# vss_adapter.net
KiCad netlist of a schematic drawn in EAGLE
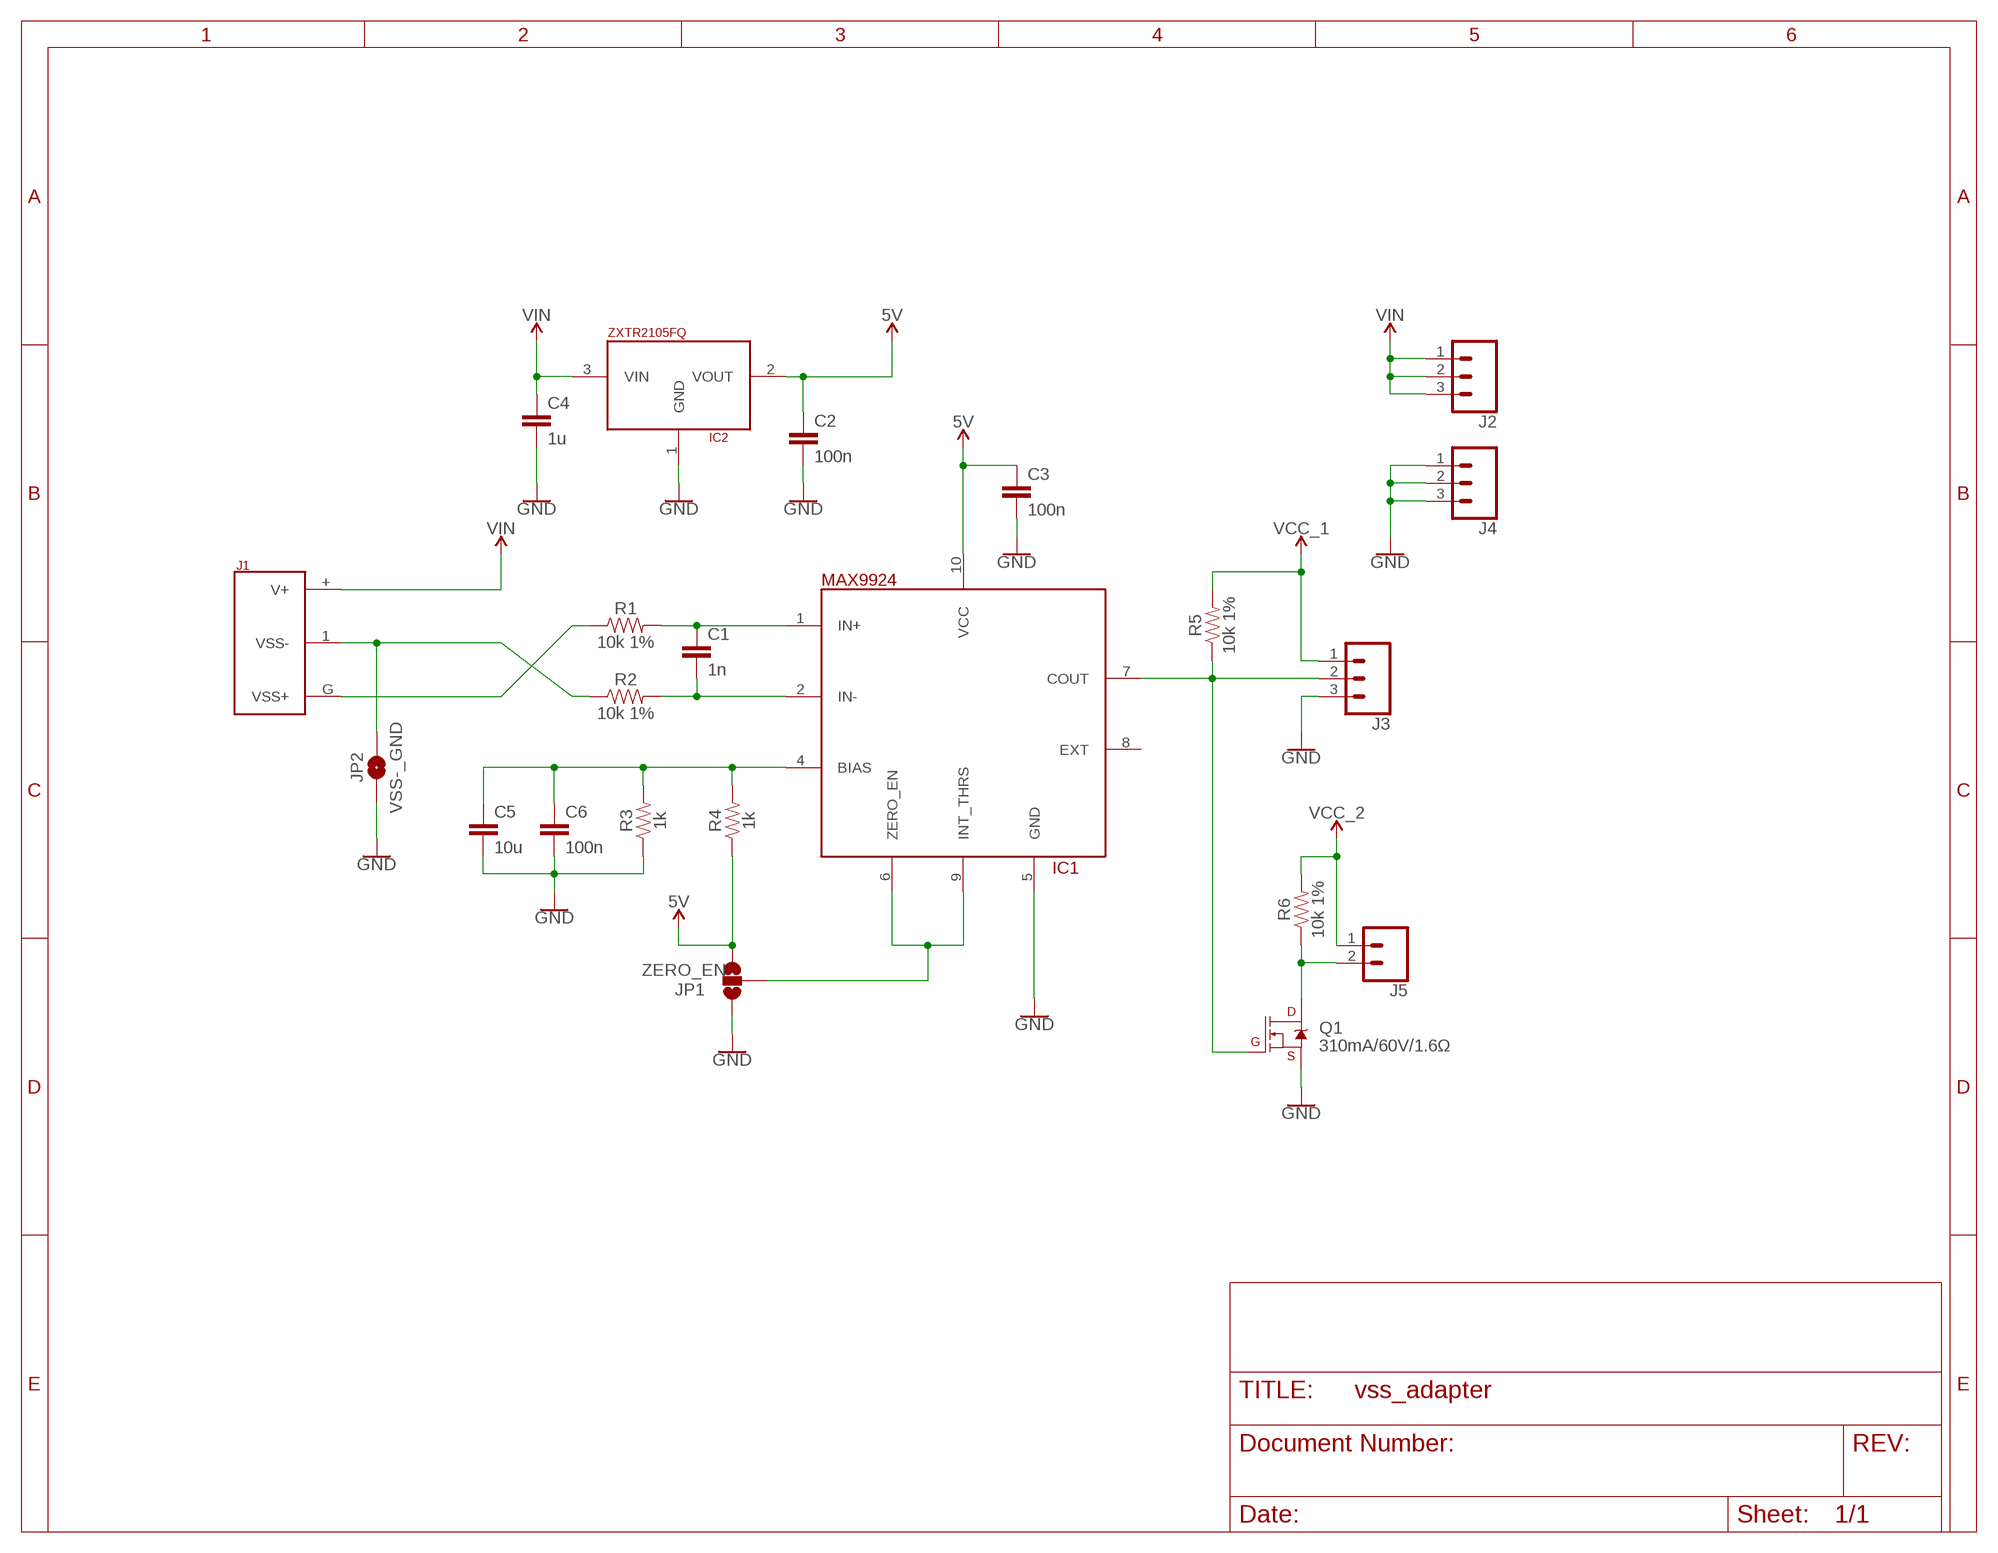
[diagram p0: schematic, sheet 1]

(export (version "E")
  (design (tool "Eeschema 10.0.6"))
  (components
    (comp (ref "C1")
      (value "1n")
      (footprint "eagle-import:0603")
      (libsource (lib "eagle-import") (part "CL10B102KB8NNWC"))
    )
    (comp (ref "C2")
      (value "100n")
      (footprint "eagle-import:0603")
      (libsource (lib "eagle-import") (part "CL10B104MB8NNNC"))
    )
    (comp (ref "C3")
      (value "100n")
      (footprint "eagle-import:0603")
      (libsource (lib "eagle-import") (part "CL10B104MB8NNNC"))
    )
    (comp (ref "C4")
      (value "1u")
      (footprint "eagle-import:0603")
      (libsource (lib "eagle-import") (part "CL10A105KA8NNNC"))
    )
    (comp (ref "C5")
      (value "10u")
      (footprint "eagle-import:0603")
      (libsource (lib "eagle-import") (part "CL10B106MQ8NRNC"))
    )
    (comp (ref "C6")
      (value "100n")
      (footprint "eagle-import:0603")
      (libsource (lib "eagle-import") (part "CL10B104MB8NNNC"))
    )
    (comp (ref "IC1")
      (value "MAX9924")
      (footprint "eagle-import:UMAX10")
      (libsource (lib "eagle-import") (part "MAX9924"))
    )
    (comp (ref "IC2")
      (value "ZXTR2105FQ")
      (footprint "eagle-import:SOT23")
      (libsource (lib "eagle-import") (part "ZXTR2105FQ"))
    )
    (comp (ref "J1")
      (value "VOLVO_CONN_VSS")
      (footprint "eagle-import:VOLVO_CONN_VSS")
      (libsource (lib "eagle-import") (part "VOLVO_CONN_VSS"))
    )
    (comp (ref "J2")
      (value "CONN_031X03_LARGE")
      (footprint "eagle-import:1X03_LARGE")
      (libsource (lib "eagle-import") (part "CONN_031X03_LARGE"))
    )
    (comp (ref "J3")
      (value "CONN_031X03_LARGE")
      (footprint "eagle-import:1X03_LARGE")
      (libsource (lib "eagle-import") (part "CONN_031X03_LARGE"))
    )
    (comp (ref "J4")
      (value "CONN_031X03_LARGE")
      (footprint "eagle-import:1X03_LARGE")
      (libsource (lib "eagle-import") (part "CONN_031X03_LARGE"))
    )
    (comp (ref "J5")
      (value "CONN_02LARGE")
      (footprint "eagle-import:1X02_LARGE")
      (libsource (lib "eagle-import") (part "CONN_02LARGE"))
    )
    (comp (ref "JP1")
      (value "ZERO_EN")
      (footprint "eagle-import:SMT-JUMPER_3_NO_SILK")
      (libsource (lib "eagle-import") (part "JUMPER-SMT_3_NO_SILK"))
    )
    (comp (ref "JP2")
      (value "VSS-_GND")
      (footprint "eagle-import:SMT-JUMPER_2_NO_SILK")
      (libsource (lib "eagle-import") (part "JUMPER-SMT_2_NO_SILK"))
    )
    (comp (ref "Q1")
      (value "310mA/60V/1.6Ω")
      (footprint "eagle-import:SOT323")
      (libsource (lib "eagle-import") (part "MOSFET-NCH-2N7002PW"))
    )
    (comp (ref "R1")
      (value "10k 1%")
      (footprint "eagle-import:0603")
      (libsource (lib "eagle-import") (part "RC0603FR-1010KL"))
    )
    (comp (ref "R2")
      (value "10k 1%")
      (footprint "eagle-import:0603")
      (libsource (lib "eagle-import") (part "RC0603FR-1010KL"))
    )
    (comp (ref "R3")
      (value "1k")
      (footprint "eagle-import:0603")
      (libsource (lib "eagle-import") (part "RC0603JR-071KL"))
    )
    (comp (ref "R4")
      (value "1k")
      (footprint "eagle-import:0603")
      (libsource (lib "eagle-import") (part "RC0603JR-071KL"))
    )
    (comp (ref "R5")
      (value "10k 1%")
      (footprint "eagle-import:0603")
      (libsource (lib "eagle-import") (part "RC0603FR-1010KL"))
    )
    (comp (ref "R6")
      (value "10k 1%")
      (footprint "eagle-import:0603")
      (libsource (lib "eagle-import") (part "RC0603FR-1010KL"))
    )
  )
  (nets
    (net (code "1") (name "5V") (class "Default")
      (node (ref "C2") (pin "1") (pinfunction "1_1") (pintype "passive"))
      (node (ref "C3") (pin "1") (pinfunction "1_1") (pintype "passive"))
      (node (ref "IC1") (pin "10") (pinfunction "VCC_10") (pintype "bidirectional"))
      (node (ref "IC2") (pin "2") (pinfunction "VOUT_2") (pintype "bidirectional"))
      (node (ref "JP1") (pin "3") (pinfunction "3_3") (pintype "passive"))
      (node (ref "R4") (pin "1") (pinfunction "1_1") (pintype "passive"))
    )
    (net (code "2") (name "GND") (class "Default")
      (node (ref "C2") (pin "2") (pinfunction "2_2") (pintype "passive"))
      (node (ref "C3") (pin "2") (pinfunction "2_2") (pintype "passive"))
      (node (ref "C4") (pin "2") (pinfunction "2_2") (pintype "passive"))
      (node (ref "C5") (pin "2") (pinfunction "2_2") (pintype "passive"))
      (node (ref "C6") (pin "2") (pinfunction "2_2") (pintype "passive"))
      (node (ref "IC1") (pin "5") (pinfunction "GND_5") (pintype "bidirectional"))
      (node (ref "IC2") (pin "1") (pinfunction "GND_1") (pintype "bidirectional"))
      (node (ref "J3") (pin "3") (pinfunction "3_3") (pintype "passive"))
      (node (ref "J4") (pin "1") (pinfunction "1_1") (pintype "passive"))
      (node (ref "J4") (pin "2") (pinfunction "2_2") (pintype "passive"))
      (node (ref "J4") (pin "3") (pinfunction "3_3") (pintype "passive"))
      (node (ref "JP1") (pin "1") (pinfunction "1_1") (pintype "passive"))
      (node (ref "JP2") (pin "1") (pinfunction "1_1") (pintype "passive"))
      (node (ref "Q1") (pin "2") (pinfunction "S_2") (pintype "bidirectional"))
      (node (ref "R3") (pin "1") (pinfunction "1_1") (pintype "passive"))
    )
    (net (code "3") (name "Net-(IC1-BIAS)") (class "Default")
      (node (ref "C5") (pin "1") (pinfunction "1_1") (pintype "passive"))
      (node (ref "C6") (pin "1") (pinfunction "1_1") (pintype "passive"))
      (node (ref "IC1") (pin "4") (pinfunction "BIAS_4") (pintype "bidirectional"))
      (node (ref "R3") (pin "2") (pinfunction "2_2") (pintype "passive"))
      (node (ref "R4") (pin "2") (pinfunction "2_2") (pintype "passive"))
    )
    (net (code "4") (name "Net-(IC1-COUT)") (class "Default")
      (node (ref "IC1") (pin "7") (pinfunction "COUT_7") (pintype "bidirectional"))
      (node (ref "J3") (pin "2") (pinfunction "2_2") (pintype "passive"))
      (node (ref "Q1") (pin "1") (pinfunction "G_1") (pintype "bidirectional"))
      (node (ref "R5") (pin "1") (pinfunction "1_1") (pintype "passive"))
    )
    (net (code "5") (name "Net-(IC1-IN+)") (class "Default")
      (node (ref "C1") (pin "1") (pinfunction "1_1") (pintype "passive"))
      (node (ref "IC1") (pin "1") (pinfunction "IN+_1") (pintype "bidirectional"))
      (node (ref "R1") (pin "2") (pinfunction "2_2") (pintype "passive"))
    )
    (net (code "6") (name "Net-(IC1-IN-)") (class "Default")
      (node (ref "C1") (pin "2") (pinfunction "2_2") (pintype "passive"))
      (node (ref "IC1") (pin "2") (pinfunction "IN-_2") (pintype "bidirectional"))
      (node (ref "R2") (pin "2") (pinfunction "2_2") (pintype "passive"))
    )
    (net (code "7") (name "Net-(IC1-INT_THRS)") (class "Default")
      (node (ref "IC1") (pin "6") (pinfunction "ZERO_EN_6") (pintype "bidirectional"))
      (node (ref "IC1") (pin "9") (pinfunction "INT_THRS_9") (pintype "bidirectional"))
      (node (ref "JP1") (pin "2") (pinfunction "2_2") (pintype "passive"))
    )
    (net (code "8") (name "Net-(J1-VSS+)") (class "Default")
      (node (ref "J1") (pin "G") (pinfunction "VSS+_G") (pintype "bidirectional"))
      (node (ref "R1") (pin "1") (pinfunction "1_1") (pintype "passive"))
    )
    (net (code "9") (name "Net-(J1-VSS-)") (class "Default")
      (node (ref "J1") (pin "1") (pinfunction "VSS-_1") (pintype "bidirectional"))
      (node (ref "JP2") (pin "2") (pinfunction "2_2") (pintype "passive"))
      (node (ref "R2") (pin "1") (pinfunction "1_1") (pintype "passive"))
    )
    (net (code "10") (name "Net-(Q1-D)") (class "Default")
      (node (ref "J5") (pin "2") (pinfunction "2_2") (pintype "passive"))
      (node (ref "Q1") (pin "3") (pinfunction "D_3") (pintype "bidirectional"))
      (node (ref "R6") (pin "1") (pinfunction "1_1") (pintype "passive"))
    )
    (net (code "11") (name "VCC_1") (class "Default")
      (node (ref "J3") (pin "1") (pinfunction "1_1") (pintype "passive"))
      (node (ref "R5") (pin "2") (pinfunction "2_2") (pintype "passive"))
    )
    (net (code "12") (name "VCC_2") (class "Default")
      (node (ref "J5") (pin "1") (pinfunction "1_1") (pintype "passive"))
      (node (ref "R6") (pin "2") (pinfunction "2_2") (pintype "passive"))
    )
    (net (code "13") (name "VIN") (class "Default")
      (node (ref "C4") (pin "1") (pinfunction "1_1") (pintype "passive"))
      (node (ref "IC2") (pin "3") (pinfunction "VIN_3") (pintype "bidirectional"))
      (node (ref "J1") (pin "+") (pinfunction "V+_+") (pintype "bidirectional"))
      (node (ref "J2") (pin "1") (pinfunction "1_1") (pintype "passive"))
      (node (ref "J2") (pin "2") (pinfunction "2_2") (pintype "passive"))
      (node (ref "J2") (pin "3") (pinfunction "3_3") (pintype "passive"))
    )
    (net (code "14") (name "unconnected-(IC1-EXT-Pad8)") (class "Default")
      (node (ref "IC1") (pin "8") (pinfunction "EXT_8") (pintype "bidirectional"))
    )
  )
)
